# PIC32MM.net
KiCad netlist of a schematic drawn in Altium Designer
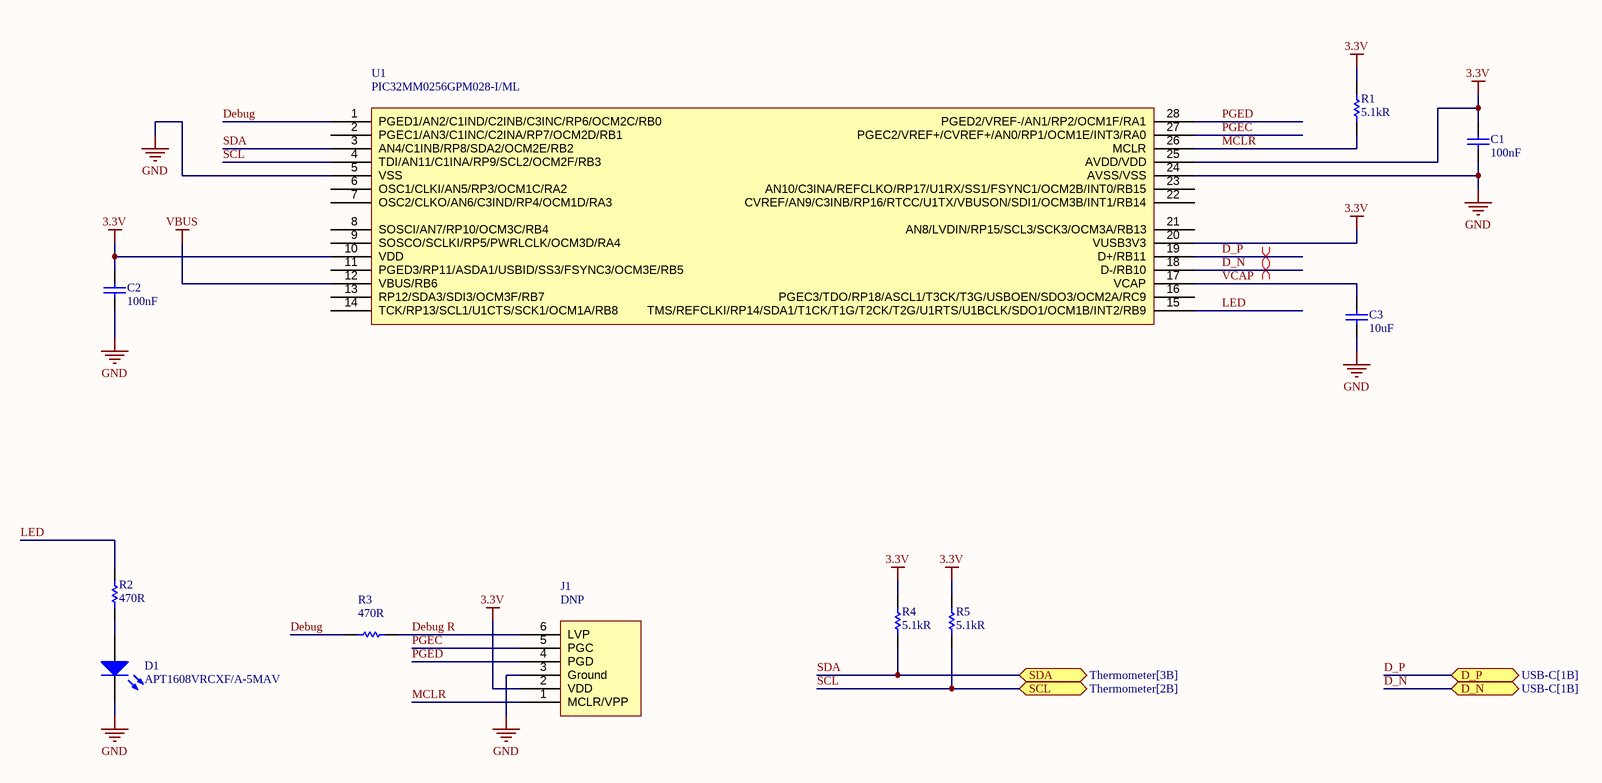
[diagram p0: PIC32MM.SchDoc]

(export (version "E")
  (design (tool "Eeschema 10.0.6"))
  (components
    (comp (ref "C1") (value "100nF") (footprint "Capacitor 0402") (libsource (lib "x-io") (part "Capacitor")))
    (comp (ref "C2") (value "100nF") (footprint "Capacitor 0402") (libsource (lib "x-io") (part "Capacitor")))
    (comp (ref "C3") (value "10uF") (footprint "Capacitor 0402") (libsource (lib "x-io") (part "Capacitor")))
    (comp (ref "D1")
      (value "APT1608VRCXF/A-5MAV")
      (footprint "LED 0603")
      (libsource (lib "x-io") (part "LED"))
    )
    (comp (ref "J1")
      (value "DNP")
      (footprint "Tag Connect No Legs")
      (libsource (lib "x-io") (part "MPLAB ICSP"))
    )
    (comp (ref "R1") (value "5.1kR") (footprint "Resistor 0402") (libsource (lib "x-io") (part "Resistor")))
    (comp (ref "R2") (value "470R") (footprint "Resistor 0402") (libsource (lib "x-io") (part "Resistor")))
    (comp (ref "R3") (value "470R") (footprint "Resistor 0402") (libsource (lib "x-io") (part "Resistor")))
    (comp (ref "R4") (value "5.1kR") (footprint "Resistor 0402") (libsource (lib "x-io") (part "Resistor")))
    (comp (ref "R5") (value "5.1kR") (footprint "Resistor 0402") (libsource (lib "x-io") (part "Resistor")))
    (comp (ref "U1")
      (value "PIC32MM0256GPM028-I/ML")
      (footprint "QFN-28")
      (libsource (lib "x-io") (part "PIC32MM0256GPM028-I/ML"))
    )
  )
  (nets
    (net (code "1") (name "/D_N") (class "Default")
      (node (ref "U1") (pin "18") (pinfunction "D-/RB10_18") (pintype "passive"))
    )
    (net (code "2") (name "/D_P") (class "Default")
      (node (ref "U1") (pin "19") (pinfunction "D+/RB11_19") (pintype "passive"))
    )
    (net (code "3") (name "/Debug") (class "Default")
      (node (ref "R3") (pin "2") (pinfunction "2_2") (pintype "passive"))
      (node (ref "U1") (pin "1") (pinfunction "PGED1/AN2/C1IND/C2INB/C3INC/RP6/OCM2C/RB0_1") (pintype "passive"))
    )
    (net (code "4") (name "/Debug R") (class "Default")
      (node (ref "J1") (pin "6") (pinfunction "LVP_6") (pintype "passive"))
      (node (ref "R3") (pin "1") (pinfunction "1_1") (pintype "passive"))
    )
    (net (code "5") (name "/LED") (class "Default")
      (node (ref "R2") (pin "2") (pinfunction "2_2") (pintype "passive"))
      (node (ref "U1") (pin "15") (pinfunction "TMS/REFCLKI/RP14/SDA1/T1CK/T1G/T2CK/T2G/U1RTS/U1BCLK/SDO1/OCM1B/INT2/RB9_15") (pintype "passive"))
    )
    (net (code "6") (name "/MCLR") (class "Default")
      (node (ref "J1") (pin "1") (pinfunction "MCLR/VPP_1") (pintype "passive"))
      (node (ref "R1") (pin "1") (pinfunction "1_1") (pintype "passive"))
      (node (ref "U1") (pin "26") (pinfunction "MCLR_26") (pintype "passive"))
    )
    (net (code "7") (name "/PGEC") (class "Default")
      (node (ref "J1") (pin "5") (pinfunction "PGC_5") (pintype "passive"))
      (node (ref "U1") (pin "27") (pinfunction "PGEC2/VREF+/CVREF+/AN0/RP1/OCM1E/INT3/RA0_27") (pintype "passive"))
    )
    (net (code "8") (name "/PGED") (class "Default")
      (node (ref "J1") (pin "4") (pinfunction "PGD_4") (pintype "passive"))
      (node (ref "U1") (pin "28") (pinfunction "PGED2/VREF-/AN1/RP2/OCM1F/RA1_28") (pintype "passive"))
    )
    (net (code "9") (name "/SCL") (class "Default")
      (node (ref "R5") (pin "1") (pinfunction "1_1") (pintype "passive"))
      (node (ref "U1") (pin "4") (pinfunction "TDI/AN11/C1INA/RP9/SCL2/OCM2F/RB3_4") (pintype "passive"))
    )
    (net (code "10") (name "/SDA") (class "Default")
      (node (ref "R4") (pin "1") (pinfunction "1_1") (pintype "passive"))
      (node (ref "U1") (pin "3") (pinfunction "AN4/C1INB/RP8/SDA2/OCM2E/RB2_3") (pintype "passive"))
    )
    (net (code "11") (name "/VCAP") (class "Default")
      (node (ref "C3") (pin "2") (pinfunction "2_2") (pintype "passive"))
      (node (ref "U1") (pin "17") (pinfunction "VCAP_17") (pintype "passive"))
    )
    (net (code "12") (name "3.3V") (class "Default")
      (node (ref "C1") (pin "2") (pinfunction "2_2") (pintype "passive"))
      (node (ref "C2") (pin "2") (pinfunction "2_2") (pintype "passive"))
      (node (ref "J1") (pin "2") (pinfunction "VDD_2") (pintype "passive"))
      (node (ref "R1") (pin "2") (pinfunction "2_2") (pintype "passive"))
      (node (ref "R4") (pin "2") (pinfunction "2_2") (pintype "passive"))
      (node (ref "R5") (pin "2") (pinfunction "2_2") (pintype "passive"))
      (node (ref "U1") (pin "10") (pinfunction "VDD_10") (pintype "passive"))
      (node (ref "U1") (pin "20") (pinfunction "VUSB3V3_20") (pintype "passive"))
      (node (ref "U1") (pin "25") (pinfunction "AVDD/VDD_25") (pintype "passive"))
    )
    (net (code "13") (name "GND") (class "Default")
      (node (ref "C1") (pin "1") (pinfunction "1_1") (pintype "passive"))
      (node (ref "C2") (pin "1") (pinfunction "1_1") (pintype "passive"))
      (node (ref "C3") (pin "1") (pinfunction "1_1") (pintype "passive"))
      (node (ref "D1") (pin "K") (pinfunction "K_K") (pintype "passive"))
      (node (ref "J1") (pin "3") (pinfunction "Ground_3") (pintype "passive"))
      (node (ref "U1") (pin "24") (pinfunction "AVSS/VSS_24") (pintype "passive"))
      (node (ref "U1") (pin "5") (pinfunction "VSS_5") (pintype "passive"))
    )
    (net (code "14") (name "Net-(D1-PadA)") (class "Default")
      (node (ref "D1") (pin "A") (pinfunction "A_A") (pintype "passive"))
      (node (ref "R2") (pin "1") (pinfunction "1_1") (pintype "passive"))
    )
    (net (code "15") (name "VBUS") (class "Default")
      (node (ref "U1") (pin "12") (pinfunction "VBUS/RB6_12") (pintype "passive"))
    )
    (net (code "16") (name "unconnected-(U1-AN8{slash}LVDIN{slash}RP15{slash}SCL3{slash}SCK3{slash}OCM3A{slash}RB13-Pad21)") (class "Default")
      (node (ref "U1") (pin "21") (pinfunction "AN8/LVDIN/RP15/SCL3/SCK3/OCM3A/RB13_21") (pintype "passive"))
    )
    (net (code "17") (name "unconnected-(U1-AN10{slash}C3INA{slash}REFCLKO{slash}RP17{slash}U1RX{slash}SS1{slash}FSYNC1{slash}OCM2B{slash}INT0{slash}RB15-Pad23)") (class "Default")
      (node (ref "U1") (pin "23") (pinfunction "AN10/C3INA/REFCLKO/RP17/U1RX/SS1/FSYNC1/OCM2B/INT0/RB15_23") (pintype "passive"))
    )
    (net (code "18") (name "unconnected-(U1-CVREF{slash}AN9{slash}C3INB{slash}RP16{slash}RTCC{slash}U1TX{slash}VBUSON{slash}SDI1{slash}OCM3B{slash}INT1{slash}RB14-Pad22)") (class "Default")
      (node (ref "U1") (pin "22") (pinfunction "CVREF/AN9/C3INB/RP16/RTCC/U1TX/VBUSON/SDI1/OCM3B/INT1/RB14_22") (pintype "passive"))
    )
    (net (code "19") (name "unconnected-(U1-OSC1{slash}CLKI{slash}AN5{slash}RP3{slash}OCM1C{slash}RA2-Pad6)") (class "Default")
      (node (ref "U1") (pin "6") (pinfunction "OSC1/CLKI/AN5/RP3/OCM1C/RA2_6") (pintype "passive"))
    )
    (net (code "20") (name "unconnected-(U1-OSC2{slash}CLKO{slash}AN6{slash}C3IND{slash}RP4{slash}OCM1D{slash}RA3-Pad7)") (class "Default")
      (node (ref "U1") (pin "7") (pinfunction "OSC2/CLKO/AN6/C3IND/RP4/OCM1D/RA3_7") (pintype "passive"))
    )
    (net (code "21") (name "unconnected-(U1-PGEC1{slash}AN3{slash}C1INC{slash}C2INA{slash}RP7{slash}OCM2D{slash}RB1-Pad2)") (class "Default")
      (node (ref "U1") (pin "2") (pinfunction "PGEC1/AN3/C1INC/C2INA/RP7/OCM2D/RB1_2") (pintype "passive"))
    )
    (net (code "22") (name "unconnected-(U1-PGEC3{slash}TDO{slash}RP18{slash}ASCL1{slash}T3CK{slash}T3G{slash}USBOEN{slash}SDO3{slash}OCM2A{slash}RC9-Pad16)") (class "Default")
      (node (ref "U1") (pin "16") (pinfunction "PGEC3/TDO/RP18/ASCL1/T3CK/T3G/USBOEN/SDO3/OCM2A/RC9_16") (pintype "passive"))
    )
    (net (code "23") (name "unconnected-(U1-PGED3{slash}RP11{slash}ASDA1{slash}USBID{slash}SS3{slash}FSYNC3{slash}OCM3E{slash}RB5-Pad11)") (class "Default")
      (node (ref "U1") (pin "11") (pinfunction "PGED3/RP11/ASDA1/USBID/SS3/FSYNC3/OCM3E/RB5_11") (pintype "passive"))
    )
    (net (code "24") (name "unconnected-(U1-RP12{slash}SDA3{slash}SDI3{slash}OCM3F{slash}RB7-Pad13)") (class "Default")
      (node (ref "U1") (pin "13") (pinfunction "RP12/SDA3/SDI3/OCM3F/RB7_13") (pintype "passive"))
    )
    (net (code "25") (name "unconnected-(U1-SOSCI{slash}AN7{slash}RP10{slash}OCM3C{slash}RB4-Pad8)") (class "Default")
      (node (ref "U1") (pin "8") (pinfunction "SOSCI/AN7/RP10/OCM3C/RB4_8") (pintype "passive"))
    )
    (net (code "26") (name "unconnected-(U1-SOSCO{slash}SCLKI{slash}RP5{slash}PWRLCLK{slash}OCM3D{slash}RA4-Pad9)") (class "Default")
      (node (ref "U1") (pin "9") (pinfunction "SOSCO/SCLKI/RP5/PWRLCLK/OCM3D/RA4_9") (pintype "passive"))
    )
    (net (code "27") (name "unconnected-(U1-TCK{slash}RP13{slash}SCL1{slash}U1CTS{slash}SCK1{slash}OCM1A{slash}RB8-Pad14)") (class "Default")
      (node (ref "U1") (pin "14") (pinfunction "TCK/RP13/SCL1/U1CTS/SCK1/OCM1A/RB8_14") (pintype "passive"))
    )
  )
)
